# Papilio-VGA_Wing-v10.net
KiCad netlist of a schematic drawn in EAGLE
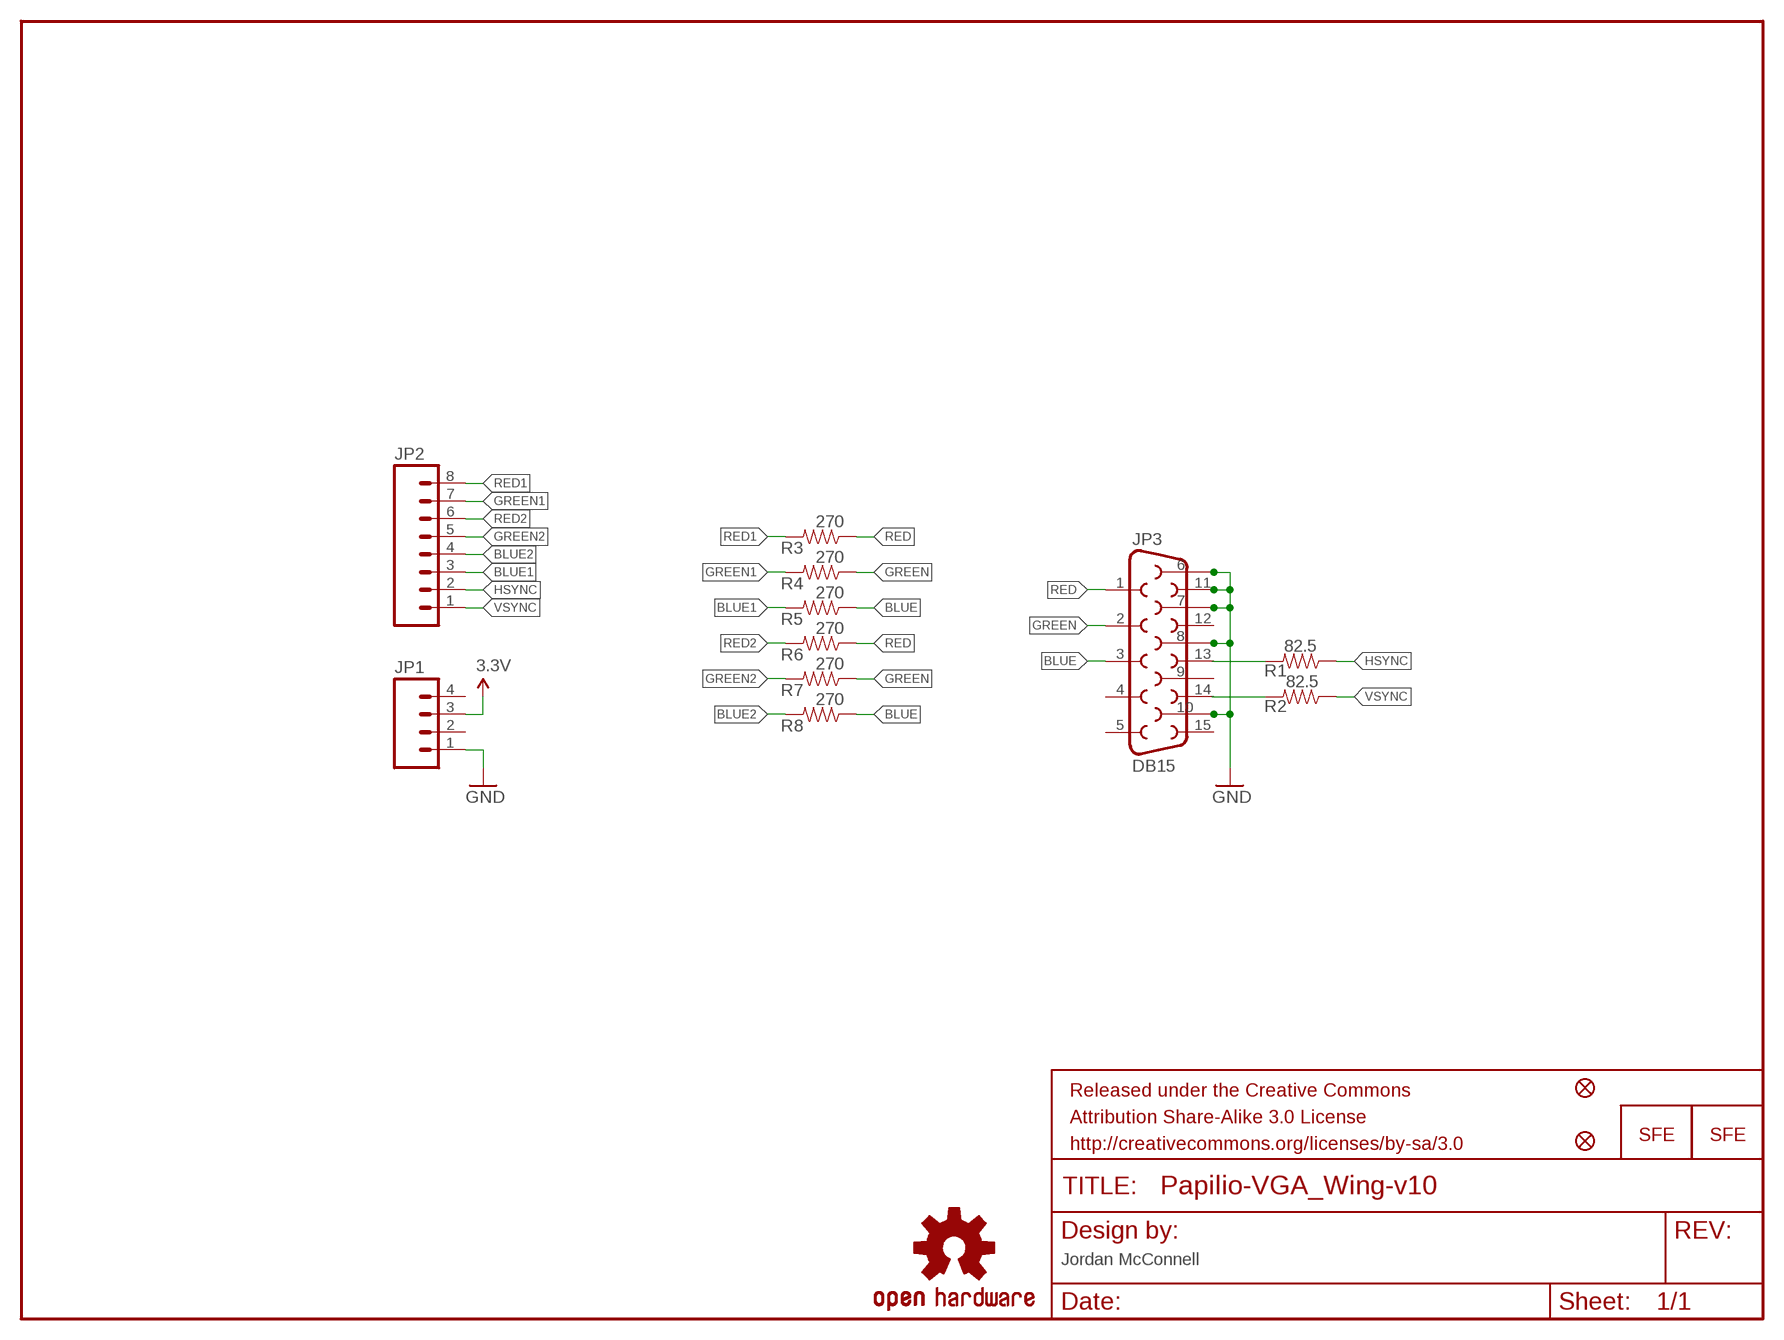
[diagram p0: schematic, sheet 1]

(export (version "E")
  (design (tool "Eeschema 10.0.6"))
  (components
    (comp (ref "FRAME1")
      (value "FRAME-LETTER")
      (footprint "eagle-import:CREATIVE_COMMONS")
      (libsource (lib "eagle-import") (part "FRAME-LETTER"))
    )
    (comp (ref "JP1")
      (value "M04PTH")
      (footprint "eagle-import:1X04")
      (libsource (lib "eagle-import") (part "M04PTH"))
    )
    (comp (ref "JP2")
      (value "M081X08")
      (footprint "eagle-import:1X08")
      (libsource (lib "eagle-import") (part "M081X08"))
    )
    (comp (ref "JP3")
      (value "DB15")
      (footprint "eagle-import:DB15")
      (libsource (lib "eagle-import") (part "DB15"))
    )
    (comp (ref "JP4")
      (value "FIDUCIALUFIDUCIAL")
      (footprint "eagle-import:MICRO-FIDUCIAL")
      (libsource (lib "eagle-import") (part "FIDUCIALUFIDUCIAL"))
    )
    (comp (ref "JP5")
      (value "FIDUCIALUFIDUCIAL")
      (footprint "eagle-import:MICRO-FIDUCIAL")
      (libsource (lib "eagle-import") (part "FIDUCIALUFIDUCIAL"))
    )
    (comp (ref "JP6")
      (value "LOGO-SFENEW")
      (footprint "eagle-import:SFE-NEW-WEBLOGO")
      (libsource (lib "eagle-import") (part "LOGO-SFENEW"))
    )
    (comp (ref "JP7")
      (value "LOGO-SFESK")
      (footprint "eagle-import:SFE-LOGO-FLAME")
      (libsource (lib "eagle-import") (part "LOGO-SFESK"))
    )
    (comp (ref "R1")
      (value "82.5")
      (footprint "eagle-import:0402-RES")
      (libsource (lib "eagle-import") (part "RESISTOR0402-RES"))
    )
    (comp (ref "R2")
      (value "82.5")
      (footprint "eagle-import:0402-RES")
      (libsource (lib "eagle-import") (part "RESISTOR0402-RES"))
    )
    (comp (ref "R3")
      (value "270")
      (footprint "eagle-import:0402-RES")
      (libsource (lib "eagle-import") (part "RESISTOR0402-RES"))
    )
    (comp (ref "R4")
      (value "270")
      (footprint "eagle-import:0402-RES")
      (libsource (lib "eagle-import") (part "RESISTOR0402-RES"))
    )
    (comp (ref "R5")
      (value "270")
      (footprint "eagle-import:0402-RES")
      (libsource (lib "eagle-import") (part "RESISTOR0402-RES"))
    )
    (comp (ref "R6")
      (value "270")
      (footprint "eagle-import:0402-RES")
      (libsource (lib "eagle-import") (part "RESISTOR0402-RES"))
    )
    (comp (ref "R7")
      (value "270")
      (footprint "eagle-import:0402-RES")
      (libsource (lib "eagle-import") (part "RESISTOR0402-RES"))
    )
    (comp (ref "R8")
      (value "270")
      (footprint "eagle-import:0402-RES")
      (libsource (lib "eagle-import") (part "RESISTOR0402-RES"))
    )
    (comp (ref "U$1")
      (value "OSHW-LOGOS")
      (footprint "eagle-import:OSHW-LOGO-S")
      (libsource (lib "eagle-import") (part "OSHW-LOGOS"))
    )
  )
  (nets
    (net (code "1") (name "3.3V") (class "Default")
      (node (ref "JP1") (pin "3") (pinfunction "3_3") (pintype "passive"))
    )
    (net (code "2") (name "BLUE") (class "Default")
      (node (ref "JP3") (pin "3") (pinfunction "3_3") (pintype "passive"))
      (node (ref "R5") (pin "1") (pinfunction "1_1") (pintype "passive"))
      (node (ref "R8") (pin "1") (pinfunction "1_1") (pintype "passive"))
    )
    (net (code "3") (name "BLUE1") (class "Default")
      (node (ref "JP2") (pin "3") (pinfunction "3_3") (pintype "passive"))
      (node (ref "R5") (pin "2") (pinfunction "2_2") (pintype "passive"))
    )
    (net (code "4") (name "BLUE2") (class "Default")
      (node (ref "JP2") (pin "4") (pinfunction "4_4") (pintype "passive"))
      (node (ref "R8") (pin "2") (pinfunction "2_2") (pintype "passive"))
    )
    (net (code "5") (name "GND") (class "Default")
      (node (ref "JP1") (pin "1") (pinfunction "1_1") (pintype "passive"))
      (node (ref "JP3") (pin "10") (pinfunction "10_10") (pintype "passive"))
      (node (ref "JP3") (pin "11") (pinfunction "11_11") (pintype "passive"))
      (node (ref "JP3") (pin "6") (pinfunction "6_6") (pintype "passive"))
      (node (ref "JP3") (pin "7") (pinfunction "7_7") (pintype "passive"))
      (node (ref "JP3") (pin "8") (pinfunction "8_8") (pintype "passive"))
    )
    (net (code "6") (name "GREEN") (class "Default")
      (node (ref "JP3") (pin "2") (pinfunction "2_2") (pintype "passive"))
      (node (ref "R4") (pin "1") (pinfunction "1_1") (pintype "passive"))
      (node (ref "R7") (pin "1") (pinfunction "1_1") (pintype "passive"))
    )
    (net (code "7") (name "GREEN1") (class "Default")
      (node (ref "JP2") (pin "7") (pinfunction "7_7") (pintype "passive"))
      (node (ref "R4") (pin "2") (pinfunction "2_2") (pintype "passive"))
    )
    (net (code "8") (name "GREEN2") (class "Default")
      (node (ref "JP2") (pin "5") (pinfunction "5_5") (pintype "passive"))
      (node (ref "R7") (pin "2") (pinfunction "2_2") (pintype "passive"))
    )
    (net (code "9") (name "HSYNC") (class "Default")
      (node (ref "JP2") (pin "2") (pinfunction "2_2") (pintype "passive"))
      (node (ref "R1") (pin "1") (pinfunction "1_1") (pintype "passive"))
    )
    (net (code "10") (name "Net-(JP3-Pad13)") (class "Default")
      (node (ref "JP3") (pin "13") (pinfunction "13_13") (pintype "passive"))
      (node (ref "R1") (pin "2") (pinfunction "2_2") (pintype "passive"))
    )
    (net (code "11") (name "Net-(JP3-Pad14)") (class "Default")
      (node (ref "JP3") (pin "14") (pinfunction "14_14") (pintype "passive"))
      (node (ref "R2") (pin "2") (pinfunction "2_2") (pintype "passive"))
    )
    (net (code "12") (name "RED") (class "Default")
      (node (ref "JP3") (pin "1") (pinfunction "1_1") (pintype "passive"))
      (node (ref "R3") (pin "1") (pinfunction "1_1") (pintype "passive"))
      (node (ref "R6") (pin "1") (pinfunction "1_1") (pintype "passive"))
    )
    (net (code "13") (name "RED1") (class "Default")
      (node (ref "JP2") (pin "8") (pinfunction "8_8") (pintype "passive"))
      (node (ref "R3") (pin "2") (pinfunction "2_2") (pintype "passive"))
    )
    (net (code "14") (name "RED2") (class "Default")
      (node (ref "JP2") (pin "6") (pinfunction "6_6") (pintype "passive"))
      (node (ref "R6") (pin "2") (pinfunction "2_2") (pintype "passive"))
    )
    (net (code "15") (name "VSYNC") (class "Default")
      (node (ref "JP2") (pin "1") (pinfunction "1_1") (pintype "passive"))
      (node (ref "R2") (pin "1") (pinfunction "1_1") (pintype "passive"))
    )
    (net (code "16") (name "unconnected-(JP1-Pad2)") (class "Default")
      (node (ref "JP1") (pin "2") (pinfunction "2_2") (pintype "passive"))
    )
    (net (code "17") (name "unconnected-(JP1-Pad4)") (class "Default")
      (node (ref "JP1") (pin "4") (pinfunction "4_4") (pintype "passive"))
    )
    (net (code "18") (name "unconnected-(JP3-Pad4)") (class "Default")
      (node (ref "JP3") (pin "4") (pinfunction "4_4") (pintype "passive"))
    )
    (net (code "19") (name "unconnected-(JP3-Pad5)") (class "Default")
      (node (ref "JP3") (pin "5") (pinfunction "5_5") (pintype "passive"))
    )
    (net (code "20") (name "unconnected-(JP3-Pad9)") (class "Default")
      (node (ref "JP3") (pin "9") (pinfunction "9_9") (pintype "passive"))
    )
    (net (code "21") (name "unconnected-(JP3-Pad12)") (class "Default")
      (node (ref "JP3") (pin "12") (pinfunction "12_12") (pintype "passive"))
    )
    (net (code "22") (name "unconnected-(JP3-Pad15)") (class "Default")
      (node (ref "JP3") (pin "15") (pinfunction "15_15") (pintype "passive"))
    )
  )
)
